# main.net
KiCad netlist of a schematic drawn in EAGLE
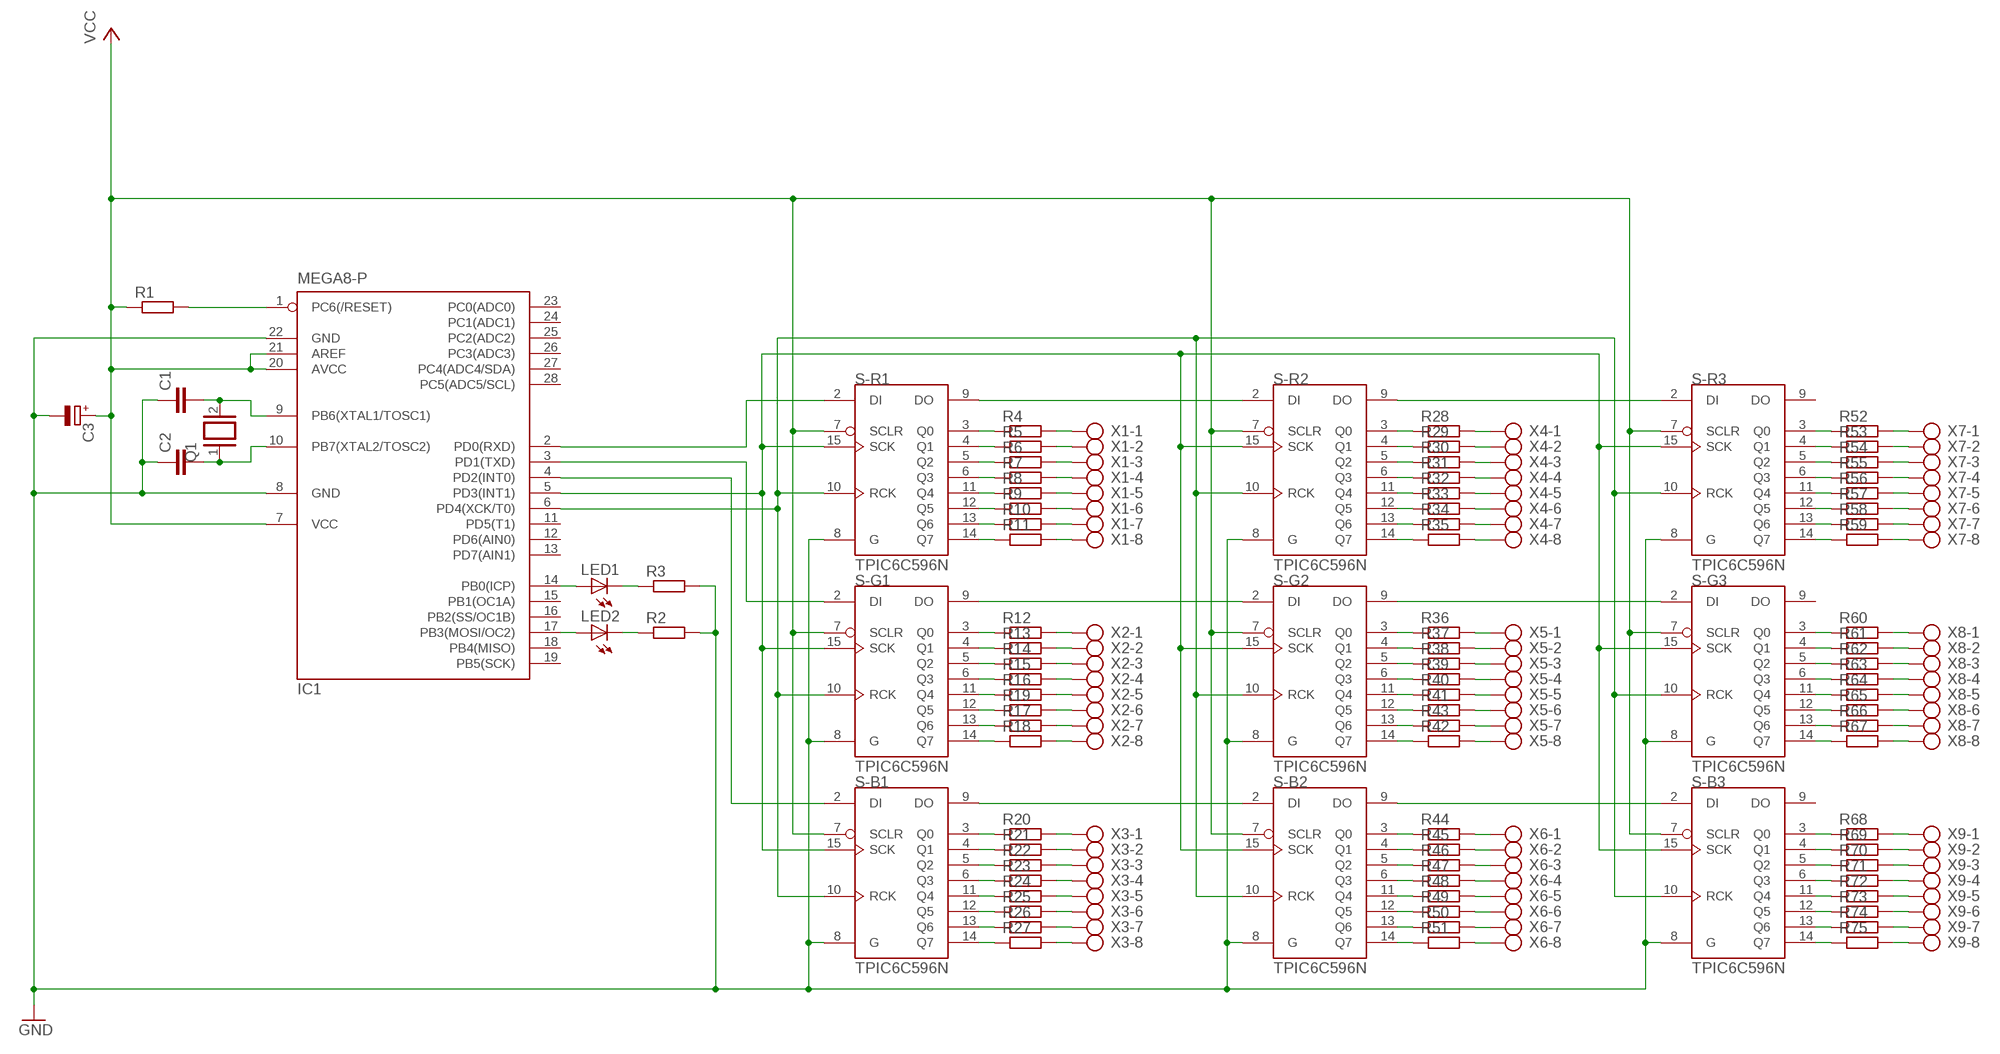
[diagram p0: schematic, sheet 1]

(export (version "E")
  (design (tool "Eeschema 10.0.6"))
  (components
    (comp (ref "C1")
      (value "C-EU025-025X050")
      (footprint "eagle-import:C025-025X050")
      (libsource (lib "eagle-import") (part "C-EU025-025X050"))
    )
    (comp (ref "C2")
      (value "C-EU025-025X050")
      (footprint "eagle-import:C025-025X050")
      (libsource (lib "eagle-import") (part "C-EU025-025X050"))
    )
    (comp (ref "C3")
      (value "CPOL-EUE2.5-7")
      (footprint "eagle-import:E2,5-7")
      (libsource (lib "eagle-import") (part "CPOL-EUE2.5-7"))
    )
    (comp (ref "IC1")
      (value "MEGA8-P")
      (footprint "eagle-import:DIL28-3")
      (libsource (lib "eagle-import") (part "MEGA8-P"))
    )
    (comp (ref "LED1")
      (value "LED3MM")
      (footprint "eagle-import:LED3MM")
      (libsource (lib "eagle-import") (part "LED3MM"))
    )
    (comp (ref "LED2")
      (value "LED3MM")
      (footprint "eagle-import:LED3MM")
      (libsource (lib "eagle-import") (part "LED3MM"))
    )
    (comp (ref "Q1")
      (value "XTAL/S")
      (footprint "eagle-import:QS")
      (libsource (lib "eagle-import") (part "XTAL/S"))
    )
    (comp (ref "R1")
      (value "R-EU_0207/2V")
      (footprint "eagle-import:0207_2V")
      (libsource (lib "eagle-import") (part "R-EU_0207/2V"))
    )
    (comp (ref "R2")
      (value "R-EU_0207/2V")
      (footprint "eagle-import:0207_2V")
      (libsource (lib "eagle-import") (part "R-EU_0207/2V"))
    )
    (comp (ref "R3")
      (value "R-EU_0207/2V")
      (footprint "eagle-import:0207_2V")
      (libsource (lib "eagle-import") (part "R-EU_0207/2V"))
    )
    (comp (ref "R4")
      (value "R-EU_0207/2V")
      (footprint "eagle-import:0207_2V")
      (libsource (lib "eagle-import") (part "R-EU_0207/2V"))
    )
    (comp (ref "R5")
      (value "R-EU_0207/2V")
      (footprint "eagle-import:0207_2V")
      (libsource (lib "eagle-import") (part "R-EU_0207/2V"))
    )
    (comp (ref "R6")
      (value "R-EU_0207/2V")
      (footprint "eagle-import:0207_2V")
      (libsource (lib "eagle-import") (part "R-EU_0207/2V"))
    )
    (comp (ref "R7")
      (value "R-EU_0207/2V")
      (footprint "eagle-import:0207_2V")
      (libsource (lib "eagle-import") (part "R-EU_0207/2V"))
    )
    (comp (ref "R8")
      (value "R-EU_0207/2V")
      (footprint "eagle-import:0207_2V")
      (libsource (lib "eagle-import") (part "R-EU_0207/2V"))
    )
    (comp (ref "R9")
      (value "R-EU_0207/2V")
      (footprint "eagle-import:0207_2V")
      (libsource (lib "eagle-import") (part "R-EU_0207/2V"))
    )
    (comp (ref "R10")
      (value "R-EU_0207/2V")
      (footprint "eagle-import:0207_2V")
      (libsource (lib "eagle-import") (part "R-EU_0207/2V"))
    )
    (comp (ref "R11")
      (value "R-EU_0207/2V")
      (footprint "eagle-import:0207_2V")
      (libsource (lib "eagle-import") (part "R-EU_0207/2V"))
    )
    (comp (ref "R12")
      (value "R-EU_0207/2V")
      (footprint "eagle-import:0207_2V")
      (libsource (lib "eagle-import") (part "R-EU_0207/2V"))
    )
    (comp (ref "R13")
      (value "R-EU_0207/2V")
      (footprint "eagle-import:0207_2V")
      (libsource (lib "eagle-import") (part "R-EU_0207/2V"))
    )
    (comp (ref "R14")
      (value "R-EU_0207/2V")
      (footprint "eagle-import:0207_2V")
      (libsource (lib "eagle-import") (part "R-EU_0207/2V"))
    )
    (comp (ref "R15")
      (value "R-EU_0207/2V")
      (footprint "eagle-import:0207_2V")
      (libsource (lib "eagle-import") (part "R-EU_0207/2V"))
    )
    (comp (ref "R16")
      (value "R-EU_0207/2V")
      (footprint "eagle-import:0207_2V")
      (libsource (lib "eagle-import") (part "R-EU_0207/2V"))
    )
    (comp (ref "R17")
      (value "R-EU_0207/2V")
      (footprint "eagle-import:0207_2V")
      (libsource (lib "eagle-import") (part "R-EU_0207/2V"))
    )
    (comp (ref "R18")
      (value "R-EU_0207/2V")
      (footprint "eagle-import:0207_2V")
      (libsource (lib "eagle-import") (part "R-EU_0207/2V"))
    )
    (comp (ref "R19")
      (value "R-EU_0207/2V")
      (footprint "eagle-import:0207_2V")
      (libsource (lib "eagle-import") (part "R-EU_0207/2V"))
    )
    (comp (ref "R20")
      (value "R-EU_0207/2V")
      (footprint "eagle-import:0207_2V")
      (libsource (lib "eagle-import") (part "R-EU_0207/2V"))
    )
    (comp (ref "R21")
      (value "R-EU_0207/2V")
      (footprint "eagle-import:0207_2V")
      (libsource (lib "eagle-import") (part "R-EU_0207/2V"))
    )
    (comp (ref "R22")
      (value "R-EU_0207/2V")
      (footprint "eagle-import:0207_2V")
      (libsource (lib "eagle-import") (part "R-EU_0207/2V"))
    )
    (comp (ref "R23")
      (value "R-EU_0207/2V")
      (footprint "eagle-import:0207_2V")
      (libsource (lib "eagle-import") (part "R-EU_0207/2V"))
    )
    (comp (ref "R24")
      (value "R-EU_0207/2V")
      (footprint "eagle-import:0207_2V")
      (libsource (lib "eagle-import") (part "R-EU_0207/2V"))
    )
    (comp (ref "R25")
      (value "R-EU_0207/2V")
      (footprint "eagle-import:0207_2V")
      (libsource (lib "eagle-import") (part "R-EU_0207/2V"))
    )
    (comp (ref "R26")
      (value "R-EU_0207/2V")
      (footprint "eagle-import:0207_2V")
      (libsource (lib "eagle-import") (part "R-EU_0207/2V"))
    )
    (comp (ref "R27")
      (value "R-EU_0207/2V")
      (footprint "eagle-import:0207_2V")
      (libsource (lib "eagle-import") (part "R-EU_0207/2V"))
    )
    (comp (ref "R28")
      (value "R-EU_0207/2V")
      (footprint "eagle-import:0207_2V")
      (libsource (lib "eagle-import") (part "R-EU_0207/2V"))
    )
    (comp (ref "R29")
      (value "R-EU_0207/2V")
      (footprint "eagle-import:0207_2V")
      (libsource (lib "eagle-import") (part "R-EU_0207/2V"))
    )
    (comp (ref "R30")
      (value "R-EU_0207/2V")
      (footprint "eagle-import:0207_2V")
      (libsource (lib "eagle-import") (part "R-EU_0207/2V"))
    )
    (comp (ref "R31")
      (value "R-EU_0207/2V")
      (footprint "eagle-import:0207_2V")
      (libsource (lib "eagle-import") (part "R-EU_0207/2V"))
    )
    (comp (ref "R32")
      (value "R-EU_0207/2V")
      (footprint "eagle-import:0207_2V")
      (libsource (lib "eagle-import") (part "R-EU_0207/2V"))
    )
    (comp (ref "R33")
      (value "R-EU_0207/2V")
      (footprint "eagle-import:0207_2V")
      (libsource (lib "eagle-import") (part "R-EU_0207/2V"))
    )
    (comp (ref "R34")
      (value "R-EU_0207/2V")
      (footprint "eagle-import:0207_2V")
      (libsource (lib "eagle-import") (part "R-EU_0207/2V"))
    )
    (comp (ref "R35")
      (value "R-EU_0207/2V")
      (footprint "eagle-import:0207_2V")
      (libsource (lib "eagle-import") (part "R-EU_0207/2V"))
    )
    (comp (ref "R36")
      (value "R-EU_0207/2V")
      (footprint "eagle-import:0207_2V")
      (libsource (lib "eagle-import") (part "R-EU_0207/2V"))
    )
    (comp (ref "R37")
      (value "R-EU_0207/2V")
      (footprint "eagle-import:0207_2V")
      (libsource (lib "eagle-import") (part "R-EU_0207/2V"))
    )
    (comp (ref "R38")
      (value "R-EU_0207/2V")
      (footprint "eagle-import:0207_2V")
      (libsource (lib "eagle-import") (part "R-EU_0207/2V"))
    )
    (comp (ref "R39")
      (value "R-EU_0207/2V")
      (footprint "eagle-import:0207_2V")
      (libsource (lib "eagle-import") (part "R-EU_0207/2V"))
    )
    (comp (ref "R40")
      (value "R-EU_0207/2V")
      (footprint "eagle-import:0207_2V")
      (libsource (lib "eagle-import") (part "R-EU_0207/2V"))
    )
    (comp (ref "R41")
      (value "R-EU_0207/2V")
      (footprint "eagle-import:0207_2V")
      (libsource (lib "eagle-import") (part "R-EU_0207/2V"))
    )
    (comp (ref "R42")
      (value "R-EU_0207/2V")
      (footprint "eagle-import:0207_2V")
      (libsource (lib "eagle-import") (part "R-EU_0207/2V"))
    )
    (comp (ref "R43")
      (value "R-EU_0207/2V")
      (footprint "eagle-import:0207_2V")
      (libsource (lib "eagle-import") (part "R-EU_0207/2V"))
    )
    (comp (ref "R44")
      (value "R-EU_0207/2V")
      (footprint "eagle-import:0207_2V")
      (libsource (lib "eagle-import") (part "R-EU_0207/2V"))
    )
    (comp (ref "R45")
      (value "R-EU_0207/2V")
      (footprint "eagle-import:0207_2V")
      (libsource (lib "eagle-import") (part "R-EU_0207/2V"))
    )
    (comp (ref "R46")
      (value "R-EU_0207/2V")
      (footprint "eagle-import:0207_2V")
      (libsource (lib "eagle-import") (part "R-EU_0207/2V"))
    )
    (comp (ref "R47")
      (value "R-EU_0207/2V")
      (footprint "eagle-import:0207_2V")
      (libsource (lib "eagle-import") (part "R-EU_0207/2V"))
    )
    (comp (ref "R48")
      (value "R-EU_0207/2V")
      (footprint "eagle-import:0207_2V")
      (libsource (lib "eagle-import") (part "R-EU_0207/2V"))
    )
    (comp (ref "R49")
      (value "R-EU_0207/2V")
      (footprint "eagle-import:0207_2V")
      (libsource (lib "eagle-import") (part "R-EU_0207/2V"))
    )
    (comp (ref "R50")
      (value "R-EU_0207/2V")
      (footprint "eagle-import:0207_2V")
      (libsource (lib "eagle-import") (part "R-EU_0207/2V"))
    )
    (comp (ref "R51")
      (value "R-EU_0207/2V")
      (footprint "eagle-import:0207_2V")
      (libsource (lib "eagle-import") (part "R-EU_0207/2V"))
    )
    (comp (ref "R52")
      (value "R-EU_0207/2V")
      (footprint "eagle-import:0207_2V")
      (libsource (lib "eagle-import") (part "R-EU_0207/2V"))
    )
    (comp (ref "R53")
      (value "R-EU_0207/2V")
      (footprint "eagle-import:0207_2V")
      (libsource (lib "eagle-import") (part "R-EU_0207/2V"))
    )
    (comp (ref "R54")
      (value "R-EU_0207/2V")
      (footprint "eagle-import:0207_2V")
      (libsource (lib "eagle-import") (part "R-EU_0207/2V"))
    )
    (comp (ref "R55")
      (value "R-EU_0207/2V")
      (footprint "eagle-import:0207_2V")
      (libsource (lib "eagle-import") (part "R-EU_0207/2V"))
    )
    (comp (ref "R56")
      (value "R-EU_0207/2V")
      (footprint "eagle-import:0207_2V")
      (libsource (lib "eagle-import") (part "R-EU_0207/2V"))
    )
    (comp (ref "R57")
      (value "R-EU_0207/2V")
      (footprint "eagle-import:0207_2V")
      (libsource (lib "eagle-import") (part "R-EU_0207/2V"))
    )
    (comp (ref "R58")
      (value "R-EU_0207/2V")
      (footprint "eagle-import:0207_2V")
      (libsource (lib "eagle-import") (part "R-EU_0207/2V"))
    )
    (comp (ref "R59")
      (value "R-EU_0207/2V")
      (footprint "eagle-import:0207_2V")
      (libsource (lib "eagle-import") (part "R-EU_0207/2V"))
    )
    (comp (ref "R60")
      (value "R-EU_0207/2V")
      (footprint "eagle-import:0207_2V")
      (libsource (lib "eagle-import") (part "R-EU_0207/2V"))
    )
    (comp (ref "R61")
      (value "R-EU_0207/2V")
      (footprint "eagle-import:0207_2V")
      (libsource (lib "eagle-import") (part "R-EU_0207/2V"))
    )
    (comp (ref "R62")
      (value "R-EU_0207/2V")
      (footprint "eagle-import:0207_2V")
      (libsource (lib "eagle-import") (part "R-EU_0207/2V"))
    )
    (comp (ref "R63")
      (value "R-EU_0207/2V")
      (footprint "eagle-import:0207_2V")
      (libsource (lib "eagle-import") (part "R-EU_0207/2V"))
    )
    (comp (ref "R64")
      (value "R-EU_0207/2V")
      (footprint "eagle-import:0207_2V")
      (libsource (lib "eagle-import") (part "R-EU_0207/2V"))
    )
    (comp (ref "R65")
      (value "R-EU_0207/2V")
      (footprint "eagle-import:0207_2V")
      (libsource (lib "eagle-import") (part "R-EU_0207/2V"))
    )
    (comp (ref "R66")
      (value "R-EU_0207/2V")
      (footprint "eagle-import:0207_2V")
      (libsource (lib "eagle-import") (part "R-EU_0207/2V"))
    )
    (comp (ref "R67")
      (value "R-EU_0207/2V")
      (footprint "eagle-import:0207_2V")
      (libsource (lib "eagle-import") (part "R-EU_0207/2V"))
    )
    (comp (ref "R68")
      (value "R-EU_0207/2V")
      (footprint "eagle-import:0207_2V")
      (libsource (lib "eagle-import") (part "R-EU_0207/2V"))
    )
    (comp (ref "R69")
      (value "R-EU_0207/2V")
      (footprint "eagle-import:0207_2V")
      (libsource (lib "eagle-import") (part "R-EU_0207/2V"))
    )
    (comp (ref "R70")
      (value "R-EU_0207/2V")
      (footprint "eagle-import:0207_2V")
      (libsource (lib "eagle-import") (part "R-EU_0207/2V"))
    )
    (comp (ref "R71")
      (value "R-EU_0207/2V")
      (footprint "eagle-import:0207_2V")
      (libsource (lib "eagle-import") (part "R-EU_0207/2V"))
    )
    (comp (ref "R72")
      (value "R-EU_0207/2V")
      (footprint "eagle-import:0207_2V")
      (libsource (lib "eagle-import") (part "R-EU_0207/2V"))
    )
    (comp (ref "R73")
      (value "R-EU_0207/2V")
      (footprint "eagle-import:0207_2V")
      (libsource (lib "eagle-import") (part "R-EU_0207/2V"))
    )
    (comp (ref "R74")
      (value "R-EU_0207/2V")
      (footprint "eagle-import:0207_2V")
      (libsource (lib "eagle-import") (part "R-EU_0207/2V"))
    )
    (comp (ref "R75")
      (value "R-EU_0207/2V")
      (footprint "eagle-import:0207_2V")
      (libsource (lib "eagle-import") (part "R-EU_0207/2V"))
    )
    (comp (ref "S-B1")
      (value "TPIC6C596N")
      (footprint "eagle-import:DIL16")
      (libsource (lib "eagle-import") (part "TPIC6C596N"))
    )
    (comp (ref "S-B2")
      (value "TPIC6C596N")
      (footprint "eagle-import:DIL16")
      (libsource (lib "eagle-import") (part "TPIC6C596N"))
    )
    (comp (ref "S-B3")
      (value "TPIC6C596N")
      (footprint "eagle-import:DIL16")
      (libsource (lib "eagle-import") (part "TPIC6C596N"))
    )
    (comp (ref "S-G1")
      (value "TPIC6C596N")
      (footprint "eagle-import:DIL16")
      (libsource (lib "eagle-import") (part "TPIC6C596N"))
    )
    (comp (ref "S-G2")
      (value "TPIC6C596N")
      (footprint "eagle-import:DIL16")
      (libsource (lib "eagle-import") (part "TPIC6C596N"))
    )
    (comp (ref "S-G3")
      (value "TPIC6C596N")
      (footprint "eagle-import:DIL16")
      (libsource (lib "eagle-import") (part "TPIC6C596N"))
    )
    (comp (ref "S-R1")
      (value "TPIC6C596N")
      (footprint "eagle-import:DIL16")
      (libsource (lib "eagle-import") (part "TPIC6C596N"))
    )
    (comp (ref "S-R2")
      (value "TPIC6C596N")
      (footprint "eagle-import:DIL16")
      (libsource (lib "eagle-import") (part "TPIC6C596N"))
    )
    (comp (ref "S-R3")
      (value "TPIC6C596N")
      (footprint "eagle-import:DIL16")
      (libsource (lib "eagle-import") (part "TPIC6C596N"))
    )
    (comp (ref "X1")
      (value "AK500/8-H")
      (footprint "eagle-import:AK500_8-H")
      (libsource (lib "eagle-import") (part "AK500/8-H"))
    )
    (comp (ref "X2")
      (value "AK500/8-H")
      (footprint "eagle-import:AK500_8-H")
      (libsource (lib "eagle-import") (part "AK500/8-H"))
    )
    (comp (ref "X3")
      (value "AK500/8-H")
      (footprint "eagle-import:AK500_8-H")
      (libsource (lib "eagle-import") (part "AK500/8-H"))
    )
    (comp (ref "X4")
      (value "AK500/8-H")
      (footprint "eagle-import:AK500_8-H")
      (libsource (lib "eagle-import") (part "AK500/8-H"))
    )
    (comp (ref "X5")
      (value "AK500/8-H")
      (footprint "eagle-import:AK500_8-H")
      (libsource (lib "eagle-import") (part "AK500/8-H"))
    )
    (comp (ref "X6")
      (value "AK500/8-H")
      (footprint "eagle-import:AK500_8-H")
      (libsource (lib "eagle-import") (part "AK500/8-H"))
    )
    (comp (ref "X7")
      (value "AK500/8-H")
      (footprint "eagle-import:AK500_8-H")
      (libsource (lib "eagle-import") (part "AK500/8-H"))
    )
    (comp (ref "X8")
      (value "AK500/8-H")
      (footprint "eagle-import:AK500_8-H")
      (libsource (lib "eagle-import") (part "AK500/8-H"))
    )
    (comp (ref "X9")
      (value "AK500/8-H")
      (footprint "eagle-import:AK500_8-H")
      (libsource (lib "eagle-import") (part "AK500/8-H"))
    )
  )
  (nets
    (net (code "1") (name "GND") (class "Default")
      (node (ref "C1") (pin "1") (pinfunction "1_1") (pintype "passive"))
      (node (ref "C2") (pin "1") (pinfunction "1_1") (pintype "passive"))
      (node (ref "C3") (pin "-") (pinfunction "-_-") (pintype "passive"))
      (node (ref "IC1") (pin "22") (pinfunction "GND_22") (pintype "power_in"))
      (node (ref "IC1") (pin "8") (pinfunction "GND_8") (pintype "power_in"))
      (node (ref "R2") (pin "2") (pinfunction "2_2") (pintype "passive"))
      (node (ref "R3") (pin "2") (pinfunction "2_2") (pintype "passive"))
      (node (ref "S-B1") (pin "8") (pinfunction "G_8") (pintype "input"))
      (node (ref "S-B2") (pin "8") (pinfunction "G_8") (pintype "input"))
      (node (ref "S-B3") (pin "8") (pinfunction "G_8") (pintype "input"))
      (node (ref "S-G1") (pin "8") (pinfunction "G_8") (pintype "input"))
      (node (ref "S-G2") (pin "8") (pinfunction "G_8") (pintype "input"))
      (node (ref "S-G3") (pin "8") (pinfunction "G_8") (pintype "input"))
      (node (ref "S-R1") (pin "8") (pinfunction "G_8") (pintype "input"))
      (node (ref "S-R2") (pin "8") (pinfunction "G_8") (pintype "input"))
      (node (ref "S-R3") (pin "8") (pinfunction "G_8") (pintype "input"))
    )
    (net (code "2") (name "Net-(IC1-PB0(ICP))") (class "Default")
      (node (ref "IC1") (pin "14") (pinfunction "PB0(ICP)_14") (pintype "bidirectional"))
      (node (ref "LED1") (pin "A") (pinfunction "A_A") (pintype "passive"))
    )
    (net (code "3") (name "Net-(IC1-PB3(MOSI{slash}OC2))") (class "Default")
      (node (ref "IC1") (pin "17") (pinfunction "PB3(MOSI/OC2)_17") (pintype "bidirectional"))
      (node (ref "LED2") (pin "A") (pinfunction "A_A") (pintype "passive"))
    )
    (net (code "4") (name "Net-(IC1-PB6(XTAL1{slash}TOSC1))") (class "Default")
      (node (ref "C1") (pin "2") (pinfunction "2_2") (pintype "passive"))
      (node (ref "IC1") (pin "9") (pinfunction "PB6(XTAL1/TOSC1)_9") (pintype "bidirectional"))
      (node (ref "Q1") (pin "2") (pinfunction "2_2") (pintype "passive"))
    )
    (net (code "5") (name "Net-(IC1-PB7(XTAL2{slash}TOSC2))") (class "Default")
      (node (ref "C2") (pin "2") (pinfunction "2_2") (pintype "passive"))
      (node (ref "IC1") (pin "10") (pinfunction "PB7(XTAL2/TOSC2)_10") (pintype "bidirectional"))
      (node (ref "Q1") (pin "1") (pinfunction "1_1") (pintype "passive"))
    )
    (net (code "6") (name "Net-(IC1-PC6({slash}RESET))") (class "Default")
      (node (ref "IC1") (pin "1") (pinfunction "PC6(/RESET)_1") (pintype "bidirectional"))
      (node (ref "R1") (pin "2") (pinfunction "2_2") (pintype "passive"))
    )
    (net (code "7") (name "Net-(IC1-PD0(RXD))") (class "Default")
      (node (ref "IC1") (pin "2") (pinfunction "PD0(RXD)_2") (pintype "bidirectional"))
      (node (ref "S-R1") (pin "2") (pinfunction "DI_2") (pintype "input"))
    )
    (net (code "8") (name "Net-(IC1-PD1(TXD))") (class "Default")
      (node (ref "IC1") (pin "3") (pinfunction "PD1(TXD)_3") (pintype "bidirectional"))
      (node (ref "S-G1") (pin "2") (pinfunction "DI_2") (pintype "input"))
    )
    (net (code "9") (name "Net-(IC1-PD2(INT0))") (class "Default")
      (node (ref "IC1") (pin "4") (pinfunction "PD2(INT0)_4") (pintype "bidirectional"))
      (node (ref "S-B1") (pin "2") (pinfunction "DI_2") (pintype "input"))
    )
    (net (code "10") (name "Net-(IC1-PD3(INT1))") (class "Default")
      (node (ref "IC1") (pin "5") (pinfunction "PD3(INT1)_5") (pintype "bidirectional"))
      (node (ref "S-B1") (pin "15") (pinfunction "SCK_15") (pintype "input"))
      (node (ref "S-B2") (pin "15") (pinfunction "SCK_15") (pintype "input"))
      (node (ref "S-B3") (pin "15") (pinfunction "SCK_15") (pintype "input"))
      (node (ref "S-G1") (pin "15") (pinfunction "SCK_15") (pintype "input"))
      (node (ref "S-G2") (pin "15") (pinfunction "SCK_15") (pintype "input"))
      (node (ref "S-G3") (pin "15") (pinfunction "SCK_15") (pintype "input"))
      (node (ref "S-R1") (pin "15") (pinfunction "SCK_15") (pintype "input"))
      (node (ref "S-R2") (pin "15") (pinfunction "SCK_15") (pintype "input"))
      (node (ref "S-R3") (pin "15") (pinfunction "SCK_15") (pintype "input"))
    )
    (net (code "11") (name "Net-(IC1-PD4(XCK{slash}T0))") (class "Default")
      (node (ref "IC1") (pin "6") (pinfunction "PD4(XCK/T0)_6") (pintype "bidirectional"))
      (node (ref "S-B1") (pin "10") (pinfunction "RCK_10") (pintype "input"))
      (node (ref "S-B2") (pin "10") (pinfunction "RCK_10") (pintype "input"))
      (node (ref "S-B3") (pin "10") (pinfunction "RCK_10") (pintype "input"))
      (node (ref "S-G1") (pin "10") (pinfunction "RCK_10") (pintype "input"))
      (node (ref "S-G2") (pin "10") (pinfunction "RCK_10") (pintype "input"))
      (node (ref "S-G3") (pin "10") (pinfunction "RCK_10") (pintype "input"))
      (node (ref "S-R1") (pin "10") (pinfunction "RCK_10") (pintype "input"))
      (node (ref "S-R2") (pin "10") (pinfunction "RCK_10") (pintype "input"))
      (node (ref "S-R3") (pin "10") (pinfunction "RCK_10") (pintype "input"))
    )
    (net (code "12") (name "Net-(LED1-C)") (class "Default")
      (node (ref "LED1") (pin "K") (pinfunction "C_K") (pintype "passive"))
      (node (ref "R3") (pin "1") (pinfunction "1_1") (pintype "passive"))
    )
    (net (code "13") (name "Net-(LED2-C)") (class "Default")
      (node (ref "LED2") (pin "K") (pinfunction "C_K") (pintype "passive"))
      (node (ref "R2") (pin "1") (pinfunction "1_1") (pintype "passive"))
    )
    (net (code "14") (name "Net-(S-B1A-DO)") (class "Default")
      (node (ref "S-B1") (pin "9") (pinfunction "DO_9") (pintype "output"))
      (node (ref "S-B2") (pin "2") (pinfunction "DI_2") (pintype "input"))
    )
    (net (code "15") (name "Net-(S-B1A-Q0)") (class "Default")
      (node (ref "R20") (pin "1") (pinfunction "1_1") (pintype "passive"))
      (node (ref "S-B1") (pin "3") (pinfunction "Q0_3") (pintype "open_collector"))
    )
    (net (code "16") (name "Net-(S-B1A-Q1)") (class "Default")
      (node (ref "R21") (pin "1") (pinfunction "1_1") (pintype "passive"))
      (node (ref "S-B1") (pin "4") (pinfunction "Q1_4") (pintype "open_collector"))
    )
    (net (code "17") (name "Net-(S-B1A-Q2)") (class "Default")
      (node (ref "R22") (pin "1") (pinfunction "1_1") (pintype "passive"))
      (node (ref "S-B1") (pin "5") (pinfunction "Q2_5") (pintype "open_collector"))
    )
    (net (code "18") (name "Net-(S-B1A-Q3)") (class "Default")
      (node (ref "R23") (pin "1") (pinfunction "1_1") (pintype "passive"))
      (node (ref "S-B1") (pin "6") (pinfunction "Q3_6") (pintype "open_collector"))
    )
    (net (code "19") (name "Net-(S-B1A-Q4)") (class "Default")
      (node (ref "R24") (pin "1") (pinfunction "1_1") (pintype "passive"))
      (node (ref "S-B1") (pin "11") (pinfunction "Q4_11") (pintype "open_collector"))
    )
    (net (code "20") (name "Net-(S-B1A-Q5)") (class "Default")
      (node (ref "R25") (pin "1") (pinfunction "1_1") (pintype "passive"))
      (node (ref "S-B1") (pin "12") (pinfunction "Q5_12") (pintype "open_collector"))
    )
    (net (code "21") (name "Net-(S-B1A-Q6)") (class "Default")
      (node (ref "R26") (pin "1") (pinfunction "1_1") (pintype "passive"))
      (node (ref "S-B1") (pin "13") (pinfunction "Q6_13") (pintype "open_collector"))
    )
    (net (code "22") (name "Net-(S-B1A-Q7)") (class "Default")
      (node (ref "R27") (pin "1") (pinfunction "1_1") (pintype "passive"))
      (node (ref "S-B1") (pin "14") (pinfunction "Q7_14") (pintype "open_collector"))
    )
    (net (code "23") (name "Net-(S-B2A-DO)") (class "Default")
      (node (ref "S-B2") (pin "9") (pinfunction "DO_9") (pintype "output"))
      (node (ref "S-B3") (pin "2") (pinfunction "DI_2") (pintype "input"))
    )
    (net (code "24") (name "Net-(S-B2A-Q0)") (class "Default")
      (node (ref "R44") (pin "1") (pinfunction "1_1") (pintype "passive"))
      (node (ref "S-B2") (pin "3") (pinfunction "Q0_3") (pintype "open_collector"))
    )
    (net (code "25") (name "Net-(S-B2A-Q1)") (class "Default")
      (node (ref "R45") (pin "1") (pinfunction "1_1") (pintype "passive"))
      (node (ref "S-B2") (pin "4") (pinfunction "Q1_4") (pintype "open_collector"))
    )
    (net (code "26") (name "Net-(S-B2A-Q2)") (class "Default")
      (node (ref "R46") (pin "1") (pinfunction "1_1") (pintype "passive"))
      (node (ref "S-B2") (pin "5") (pinfunction "Q2_5") (pintype "open_collector"))
    )
    (net (code "27") (name "Net-(S-B2A-Q3)") (class "Default")
      (node (ref "R47") (pin "1") (pinfunction "1_1") (pintype "passive"))
      (node (ref "S-B2") (pin "6") (pinfunction "Q3_6") (pintype "open_collector"))
    )
    (net (code "28") (name "Net-(S-B2A-Q4)") (class "Default")
      (node (ref "R48") (pin "1") (pinfunction "1_1") (pintype "passive"))
      (node (ref "S-B2") (pin "11") (pinfunction "Q4_11") (pintype "open_collector"))
    )
    (net (code "29") (name "Net-(S-B2A-Q5)") (class "Default")
      (node (ref "R49") (pin "1") (pinfunction "1_1") (pintype "passive"))
      (node (ref "S-B2") (pin "12") (pinfunction "Q5_12") (pintype "open_collector"))
    )
    (net (code "30") (name "Net-(S-B2A-Q6)") (class "Default")
      (node (ref "R50") (pin "1") (pinfunction "1_1") (pintype "passive"))
      (node (ref "S-B2") (pin "13") (pinfunction "Q6_13") (pintype "open_collector"))
    )
    (net (code "31") (name "Net-(S-B2A-Q7)") (class "Default")
      (node (ref "R51") (pin "1") (pinfunction "1_1") (pintype "passive"))
      (node (ref "S-B2") (pin "14") (pinfunction "Q7_14") (pintype "open_collector"))
    )
    (net (code "32") (name "Net-(S-B3A-Q0)") (class "Default")
      (node (ref "R68") (pin "1") (pinfunction "1_1") (pintype "passive"))
      (node (ref "S-B3") (pin "3") (pinfunction "Q0_3") (pintype "open_collector"))
    )
    (net (code "33") (name "Net-(S-B3A-Q1)") (class "Default")
      (node (ref "R69") (pin "1") (pinfunction "1_1") (pintype "passive"))
      (node (ref "S-B3") (pin "4") (pinfunction "Q1_4") (pintype "open_collector"))
    )
    (net (code "34") (name "Net-(S-B3A-Q2)") (class "Default")
      (node (ref "R70") (pin "1") (pinfunction "1_1") (pintype "passive"))
      (node (ref "S-B3") (pin "5") (pinfunction "Q2_5") (pintype "open_collector"))
    )
    (net (code "35") (name "Net-(S-B3A-Q3)") (class "Default")
      (node (ref "R71") (pin "1") (pinfunction "1_1") (pintype "passive"))
      (node (ref "S-B3") (pin "6") (pinfunction "Q3_6") (pintype "open_collector"))
    )
    (net (code "36") (name "Net-(S-B3A-Q4)") (class "Default")
      (node (ref "R72") (pin "1") (pinfunction "1_1") (pintype "passive"))
      (node (ref "S-B3") (pin "11") (pinfunction "Q4_11") (pintype "open_collector"))
    )
    (net (code "37") (name "Net-(S-B3A-Q5)") (class "Default")
      (node (ref "R73") (pin "1") (pinfunction "1_1") (pintype "passive"))
      (node (ref "S-B3") (pin "12") (pinfunction "Q5_12") (pintype "open_collector"))
    )
    (net (code "38") (name "Net-(S-B3A-Q6)") (class "Default")
      (node (ref "R74") (pin "1") (pinfunction "1_1") (pintype "passive"))
      (node (ref "S-B3") (pin "13") (pinfunction "Q6_13") (pintype "open_collector"))
    )
    (net (code "39") (name "Net-(S-B3A-Q7)") (class "Default")
      (node (ref "R75") (pin "1") (pinfunction "1_1") (pintype "passive"))
      (node (ref "S-B3") (pin "14") (pinfunction "Q7_14") (pintype "open_collector"))
    )
    (net (code "40") (name "Net-(S-G1A-DO)") (class "Default")
      (node (ref "S-G1") (pin "9") (pinfunction "DO_9") (pintype "output"))
      (node (ref "S-G2") (pin "2") (pinfunction "DI_2") (pintype "input"))
    )
    (net (code "41") (name "Net-(S-G1A-Q0)") (class "Default")
      (node (ref "R12") (pin "1") (pinfunction "1_1") (pintype "passive"))
      (node (ref "S-G1") (pin "3") (pinfunction "Q0_3") (pintype "open_collector"))
    )
    (net (code "42") (name "Net-(S-G1A-Q1)") (class "Default")
      (node (ref "R13") (pin "1") (pinfunction "1_1") (pintype "passive"))
      (node (ref "S-G1") (pin "4") (pinfunction "Q1_4") (pintype "open_collector"))
    )
    (net (code "43") (name "Net-(S-G1A-Q2)") (class "Default")
      (node (ref "R14") (pin "1") (pinfunction "1_1") (pintype "passive"))
      (node (ref "S-G1") (pin "5") (pinfunction "Q2_5") (pintype "open_collector"))
    )
    (net (code "44") (name "Net-(S-G1A-Q3)") (class "Default")
      (node (ref "R15") (pin "1") (pinfunction "1_1") (pintype "passive"))
      (node (ref "S-G1") (pin "6") (pinfunction "Q3_6") (pintype "open_collector"))
    )
    (net (code "45") (name "Net-(S-G1A-Q4)") (class "Default")
      (node (ref "R16") (pin "1") (pinfunction "1_1") (pintype "passive"))
      (node (ref "S-G1") (pin "11") (pinfunction "Q4_11") (pintype "open_collector"))
    )
    (net (code "46") (name "Net-(S-G1A-Q5)") (class "Default")
      (node (ref "R19") (pin "1") (pinfunction "1_1") (pintype "passive"))
      (node (ref "S-G1") (pin "12") (pinfunction "Q5_12") (pintype "open_collector"))
    )
    (net (code "47") (name "Net-(S-G1A-Q6)") (class "Default")
      (node (ref "R17") (pin "1") (pinfunction "1_1") (pintype "passive"))
      (node (ref "S-G1") (pin "13") (pinfunction "Q6_13") (pintype "open_collector"))
    )
    (net (code "48") (name "Net-(S-G1A-Q7)") (class "Default")
      (node (ref "R18") (pin "1") (pinfunction "1_1") (pintype "passive"))
      (node (ref "S-G1") (pin "14") (pinfunction "Q7_14") (pintype "open_collector"))
    )
    (net (code "49") (name "Net-(S-G2A-DO)") (class "Default")
      (node (ref "S-G2") (pin "9") (pinfunction "DO_9") (pintype "output"))
      (node (ref "S-G3") (pin "2") (pinfunction "DI_2") (pintype "input"))
    )
    (net (code "50") (name "Net-(S-G2A-Q0)") (class "Default")
      (node (ref "R36") (pin "1") (pinfunction "1_1") (pintype "passive"))
      (node (ref "S-G2") (pin "3") (pinfunction "Q0_3") (pintype "open_collector"))
    )
    (net (code "51") (name "Net-(S-G2A-Q1)") (class "Default")
      (node (ref "R37") (pin "1") (pinfunction "1_1") (pintype "passive"))
      (node (ref "S-G2") (pin "4") (pinfunction "Q1_4") (pintype "open_collector"))
    )
    (net (code "52") (name "Net-(S-G2A-Q2)") (class "Default")
      (node (ref "R38") (pin "1") (pinfunction "1_1") (pintype "passive"))
      (node (ref "S-G2") (pin "5") (pinfunction "Q2_5") (pintype "open_collector"))
    )
    (net (code "53") (name "Net-(S-G2A-Q3)") (class "Default")
      (node (ref "R39") (pin "1") (pinfunction "1_1") (pintype "passive"))
      (node (ref "S-G2") (pin "6") (pinfunction "Q3_6") (pintype "open_collector"))
    )
    (net (code "54") (name "Net-(S-G2A-Q4)") (class "Default")
      (node (ref "R40") (pin "1") (pinfunction "1_1") (pintype "passive"))
      (node (ref "S-G2") (pin "11") (pinfunction "Q4_11") (pintype "open_collector"))
    )
    (net (code "55") (name "Net-(S-G2A-Q5)") (class "Default")
      (node (ref "R41") (pin "1") (pinfunction "1_1") (pintype "passive"))
      (node (ref "S-G2") (pin "12") (pinfunction "Q5_12") (pintype "open_collector"))
    )
    (net (code "56") (name "Net-(S-G2A-Q6)") (class "Default")
      (node (ref "R43") (pin "1") (pinfunction "1_1") (pintype "passive"))
      (node (ref "S-G2") (pin "13") (pinfunction "Q6_13") (pintype "open_collector"))
    )
    (net (code "57") (name "Net-(S-G2A-Q7)") (class "Default")
      (node (ref "R42") (pin "1") (pinfunction "1_1") (pintype "passive"))
      (node (ref "S-G2") (pin "14") (pinfunction "Q7_14") (pintype "open_collector"))
    )
    (net (code "58") (name "Net-(S-G3A-Q0)") (class "Default")
      (node (ref "R60") (pin "1") (pinfunction "1_1") (pintype "passive"))
      (node (ref "S-G3") (pin "3") (pinfunction "Q0_3") (pintype "open_collector"))
    )
    (net (code "59") (name "Net-(S-G3A-Q1)") (class "Default")
      (node (ref "R61") (pin "1") (pinfunction "1_1") (pintype "passive"))
      (node (ref "S-G3") (pin "4") (pinfunction "Q1_4") (pintype "open_collector"))
    )
    (net (code "60") (name "Net-(S-G3A-Q2)") (class "Default")
      (node (ref "R62") (pin "1") (pinfunction "1_1") (pintype "passive"))
      (node (ref "S-G3") (pin "5") (pinfunction "Q2_5") (pintype "open_collector"))
    )
    (net (code "61") (name "Net-(S-G3A-Q3)") (class "Default")
      (node (ref "R63") (pin "1") (pinfunction "1_1") (pintype "passive"))
      (node (ref "S-G3") (pin "6") (pinfunction "Q3_6") (pintype "open_collector"))
    )
    (net (code "62") (name "Net-(S-G3A-Q4)") (class "Default")
      (node (ref "R64") (pin "1") (pinfunction "1_1") (pintype "passive"))
      (node (ref "S-G3") (pin "11") (pinfunction "Q4_11") (pintype "open_collector"))
    )
    (net (code "63") (name "Net-(S-G3A-Q5)") (class "Default")
      (node (ref "R65") (pin "1") (pinfunction "1_1") (pintype "passive"))
      (node (ref "S-G3") (pin "12") (pinfunction "Q5_12") (pintype "open_collector"))
    )
    (net (code "64") (name "Net-(S-G3A-Q6)") (class "Default")
      (node (ref "R66") (pin "1") (pinfunction "1_1") (pintype "passive"))
      (node (ref "S-G3") (pin "13") (pinfunction "Q6_13") (pintype "open_collector"))
    )
    (net (code "65") (name "Net-(S-G3A-Q7)") (class "Default")
      (node (ref "R67") (pin "1") (pinfunction "1_1") (pintype "passive"))
      (node (ref "S-G3") (pin "14") (pinfunction "Q7_14") (pintype "open_collector"))
    )
    (net (code "66") (name "Net-(S-R1A-DO)") (class "Default")
      (node (ref "S-R1") (pin "9") (pinfunction "DO_9") (pintype "output"))
      (node (ref "S-R2") (pin "2") (pinfunction "DI_2") (pintype "input"))
    )
    (net (code "67") (name "Net-(S-R1A-Q0)") (class "Default")
      (node (ref "R4") (pin "1") (pinfunction "1_1") (pintype "passive"))
      (node (ref "S-R1") (pin "3") (pinfunction "Q0_3") (pintype "open_collector"))
    )
    (net (code "68") (name "Net-(S-R1A-Q1)") (class "Default")
      (node (ref "R5") (pin "1") (pinfunction "1_1") (pintype "passive"))
      (node (ref "S-R1") (pin "4") (pinfunction "Q1_4") (pintype "open_collector"))
    )
    (net (code "69") (name "Net-(S-R1A-Q2)") (class "Default")
      (node (ref "R6") (pin "1") (pinfunction "1_1") (pintype "passive"))
      (node (ref "S-R1") (pin "5") (pinfunction "Q2_5") (pintype "open_collector"))
    )
    (net (code "70") (name "Net-(S-R1A-Q3)") (class "Default")
      (node (ref "R7") (pin "1") (pinfunction "1_1") (pintype "passive"))
      (node (ref "S-R1") (pin "6") (pinfunction "Q3_6") (pintype "open_collector"))
    )
    (net (code "71") (name "Net-(S-R1A-Q4)") (class "Default")
      (node (ref "R8") (pin "1") (pinfunction "1_1") (pintype "passive"))
      (node (ref "S-R1") (pin "11") (pinfunction "Q4_11") (pintype "open_collector"))
    )
    (net (code "72") (name "Net-(S-R1A-Q5)") (class "Default")
      (node (ref "R9") (pin "1") (pinfunction "1_1") (pintype "passive"))
      (node (ref "S-R1") (pin "12") (pinfunction "Q5_12") (pintype "open_collector"))
    )
    (net (code "73") (name "Net-(S-R1A-Q6)") (class "Default")
      (node (ref "R10") (pin "1") (pinfunction "1_1") (pintype "passive"))
      (node (ref "S-R1") (pin "13") (pinfunction "Q6_13") (pintype "open_collector"))
    )
    (net (code "74") (name "Net-(S-R1A-Q7)") (class "Default")
      (node (ref "R11") (pin "1") (pinfunction "1_1") (pintype "passive"))
      (node (ref "S-R1") (pin "14") (pinfunction "Q7_14") (pintype "open_collector"))
    )
    (net (code "75") (name "Net-(S-R2A-DO)") (class "Default")
      (node (ref "S-R2") (pin "9") (pinfunction "DO_9") (pintype "output"))
      (node (ref "S-R3") (pin "2") (pinfunction "DI_2") (pintype "input"))
    )
    (net (code "76") (name "Net-(S-R2A-Q0)") (class "Default")
      (node (ref "R28") (pin "1") (pinfunction "1_1") (pintype "passive"))
      (node (ref "S-R2") (pin "3") (pinfunction "Q0_3") (pintype "open_collector"))
    )
    (net (code "77") (name "Net-(S-R2A-Q1)") (class "Default")
      (node (ref "R29") (pin "1") (pinfunction "1_1") (pintype "passive"))
      (node (ref "S-R2") (pin "4") (pinfunction "Q1_4") (pintype "open_collector"))
    )
    (net (code "78") (name "Net-(S-R2A-Q2)") (class "Default")
      (node (ref "R30") (pin "1") (pinfunction "1_1") (pintype "passive"))
      (node (ref "S-R2") (pin "5") (pinfunction "Q2_5") (pintype "open_collector"))
    )
    (net (code "79") (name "Net-(S-R2A-Q3)") (class "Default")
      (node (ref "R31") (pin "1") (pinfunction "1_1") (pintype "passive"))
      (node (ref "S-R2") (pin "6") (pinfunction "Q3_6") (pintype "open_collector"))
    )
    (net (code "80") (name "Net-(S-R2A-Q4)") (class "Default")
      (node (ref "R32") (pin "1") (pinfunction "1_1") (pintype "passive"))
      (node (ref "S-R2") (pin "11") (pinfunction "Q4_11") (pintype "open_collector"))
    )
    (net (code "81") (name "Net-(S-R2A-Q5)") (class "Default")
      (node (ref "R33") (pin "1") (pinfunction "1_1") (pintype "passive"))
      (node (ref "S-R2") (pin "12") (pinfunction "Q5_12") (pintype "open_collector"))
    )
    (net (code "82") (name "Net-(S-R2A-Q6)") (class "Default")
      (node (ref "R34") (pin "1") (pinfunction "1_1") (pintype "passive"))
      (node (ref "S-R2") (pin "13") (pinfunction "Q6_13") (pintype "open_collector"))
    )
    (net (code "83") (name "Net-(S-R2A-Q7)") (class "Default")
      (node (ref "R35") (pin "1") (pinfunction "1_1") (pintype "passive"))
      (node (ref "S-R2") (pin "14") (pinfunction "Q7_14") (pintype "open_collector"))
    )
    (net (code "84") (name "Net-(S-R3A-Q0)") (class "Default")
      (node (ref "R52") (pin "1") (pinfunction "1_1") (pintype "passive"))
      (node (ref "S-R3") (pin "3") (pinfunction "Q0_3") (pintype "open_collector"))
    )
    (net (code "85") (name "Net-(S-R3A-Q1)") (class "Default")
      (node (ref "R53") (pin "1") (pinfunction "1_1") (pintype "passive"))
      (node (ref "S-R3") (pin "4") (pinfunction "Q1_4") (pintype "open_collector"))
    )
    (net (code "86") (name "Net-(S-R3A-Q2)") (class "Default")
      (node (ref "R54") (pin "1") (pinfunction "1_1") (pintype "passive"))
      (node (ref "S-R3") (pin "5") (pinfunction "Q2_5") (pintype "open_collector"))
    )
    (net (code "87") (name "Net-(S-R3A-Q3)") (class "Default")
      (node (ref "R55") (pin "1") (pinfunction "1_1") (pintype "passive"))
      (node (ref "S-R3") (pin "6") (pinfunction "Q3_6") (pintype "open_collector"))
    )
    (net (code "88") (name "Net-(S-R3A-Q4)") (class "Default")
      (node (ref "R56") (pin "1") (pinfunction "1_1") (pintype "passive"))
      (node (ref "S-R3") (pin "11") (pinfunction "Q4_11") (pintype "open_collector"))
    )
    (net (code "89") (name "Net-(S-R3A-Q5)") (class "Default")
      (node (ref "R57") (pin "1") (pinfunction "1_1") (pintype "passive"))
      (node (ref "S-R3") (pin "12") (pinfunction "Q5_12") (pintype "open_collector"))
    )
    (net (code "90") (name "Net-(S-R3A-Q6)") (class "Default")
      (node (ref "R58") (pin "1") (pinfunction "1_1") (pintype "passive"))
      (node (ref "S-R3") (pin "13") (pinfunction "Q6_13") (pintype "open_collector"))
    )
    (net (code "91") (name "Net-(S-R3A-Q7)") (class "Default")
      (node (ref "R59") (pin "1") (pinfunction "1_1") (pintype "passive"))
      (node (ref "S-R3") (pin "14") (pinfunction "Q7_14") (pintype "open_collector"))
    )
    (net (code "92") (name "Net-(X1A-KL)") (class "Default")
      (node (ref "R4") (pin "2") (pinfunction "2_2") (pintype "passive"))
      (node (ref "X1") (pin "1") (pinfunction "KL_1") (pintype "passive"))
    )
    (net (code "93") (name "Net-(X1B-KL)") (class "Default")
      (node (ref "R5") (pin "2") (pinfunction "2_2") (pintype "passive"))
      (node (ref "X1") (pin "2") (pinfunction "KL_2") (pintype "passive"))
    )
    (net (code "94") (name "Net-(X1C-KL)") (class "Default")
      (node (ref "R6") (pin "2") (pinfunction "2_2") (pintype "passive"))
      (node (ref "X1") (pin "3") (pinfunction "KL_3") (pintype "passive"))
    )
    (net (code "95") (name "Net-(X1D-KL)") (class "Default")
      (node (ref "R7") (pin "2") (pinfunction "2_2") (pintype "passive"))
      (node (ref "X1") (pin "4") (pinfunction "KL_4") (pintype "passive"))
    )
    (net (code "96") (name "Net-(X1E-KL)") (class "Default")
      (node (ref "R8") (pin "2") (pinfunction "2_2") (pintype "passive"))
      (node (ref "X1") (pin "5") (pinfunction "KL_5") (pintype "passive"))
    )
    (net (code "97") (name "Net-(X1F-KL)") (class "Default")
      (node (ref "R9") (pin "2") (pinfunction "2_2") (pintype "passive"))
      (node (ref "X1") (pin "6") (pinfunction "KL_6") (pintype "passive"))
    )
    (net (code "98") (name "Net-(X1G-KL)") (class "Default")
      (node (ref "R10") (pin "2") (pinfunction "2_2") (pintype "passive"))
      (node (ref "X1") (pin "7") (pinfunction "KL_7") (pintype "passive"))
    )
    (net (code "99") (name "Net-(X1H-KL)") (class "Default")
      (node (ref "R11") (pin "2") (pinfunction "2_2") (pintype "passive"))
      (node (ref "X1") (pin "8") (pinfunction "KL_8") (pintype "passive"))
    )
    (net (code "100") (name "Net-(X2A-KL)") (class "Default")
      (node (ref "R12") (pin "2") (pinfunction "2_2") (pintype "passive"))
      (node (ref "X2") (pin "1") (pinfunction "KL_1") (pintype "passive"))
    )
    (net (code "101") (name "Net-(X2B-KL)") (class "Default")
      (node (ref "R13") (pin "2") (pinfunction "2_2") (pintype "passive"))
      (node (ref "X2") (pin "2") (pinfunction "KL_2") (pintype "passive"))
    )
    (net (code "102") (name "Net-(X2C-KL)") (class "Default")
      (node (ref "R14") (pin "2") (pinfunction "2_2") (pintype "passive"))
      (node (ref "X2") (pin "3") (pinfunction "KL_3") (pintype "passive"))
    )
    (net (code "103") (name "Net-(X2D-KL)") (class "Default")
      (node (ref "R15") (pin "2") (pinfunction "2_2") (pintype "passive"))
      (node (ref "X2") (pin "4") (pinfunction "KL_4") (pintype "passive"))
    )
    (net (code "104") (name "Net-(X2E-KL)") (class "Default")
      (node (ref "R16") (pin "2") (pinfunction "2_2") (pintype "passive"))
      (node (ref "X2") (pin "5") (pinfunction "KL_5") (pintype "passive"))
    )
    (net (code "105") (name "Net-(X2F-KL)") (class "Default")
      (node (ref "R19") (pin "2") (pinfunction "2_2") (pintype "passive"))
      (node (ref "X2") (pin "6") (pinfunction "KL_6") (pintype "passive"))
    )
    (net (code "106") (name "Net-(X2G-KL)") (class "Default")
      (node (ref "R17") (pin "2") (pinfunction "2_2") (pintype "passive"))
      (node (ref "X2") (pin "7") (pinfunction "KL_7") (pintype "passive"))
    )
    (net (code "107") (name "Net-(X2H-KL)") (class "Default")
      (node (ref "R18") (pin "2") (pinfunction "2_2") (pintype "passive"))
      (node (ref "X2") (pin "8") (pinfunction "KL_8") (pintype "passive"))
    )
    (net (code "108") (name "Net-(X3A-KL)") (class "Default")
      (node (ref "R20") (pin "2") (pinfunction "2_2") (pintype "passive"))
      (node (ref "X3") (pin "1") (pinfunction "KL_1") (pintype "passive"))
    )
    (net (code "109") (name "Net-(X3B-KL)") (class "Default")
      (node (ref "R21") (pin "2") (pinfunction "2_2") (pintype "passive"))
      (node (ref "X3") (pin "2") (pinfunction "KL_2") (pintype "passive"))
    )
    (net (code "110") (name "Net-(X3C-KL)") (class "Default")
      (node (ref "R22") (pin "2") (pinfunction "2_2") (pintype "passive"))
      (node (ref "X3") (pin "3") (pinfunction "KL_3") (pintype "passive"))
    )
    (net (code "111") (name "Net-(X3D-KL)") (class "Default")
      (node (ref "R23") (pin "2") (pinfunction "2_2") (pintype "passive"))
      (node (ref "X3") (pin "4") (pinfunction "KL_4") (pintype "passive"))
    )
    (net (code "112") (name "Net-(X3E-KL)") (class "Default")
      (node (ref "R24") (pin "2") (pinfunction "2_2") (pintype "passive"))
      (node (ref "X3") (pin "5") (pinfunction "KL_5") (pintype "passive"))
    )
    (net (code "113") (name "Net-(X3F-KL)") (class "Default")
      (node (ref "R25") (pin "2") (pinfunction "2_2") (pintype "passive"))
      (node (ref "X3") (pin "6") (pinfunction "KL_6") (pintype "passive"))
    )
    (net (code "114") (name "Net-(X3G-KL)") (class "Default")
      (node (ref "R26") (pin "2") (pinfunction "2_2") (pintype "passive"))
      (node (ref "X3") (pin "7") (pinfunction "KL_7") (pintype "passive"))
    )
    (net (code "115") (name "Net-(X3H-KL)") (class "Default")
      (node (ref "R27") (pin "2") (pinfunction "2_2") (pintype "passive"))
      (node (ref "X3") (pin "8") (pinfunction "KL_8") (pintype "passive"))
    )
    (net (code "116") (name "Net-(X4A-KL)") (class "Default")
      (node (ref "R28") (pin "2") (pinfunction "2_2") (pintype "passive"))
      (node (ref "X4") (pin "1") (pinfunction "KL_1") (pintype "passive"))
    )
    (net (code "117") (name "Net-(X4B-KL)") (class "Default")
      (node (ref "R29") (pin "2") (pinfunction "2_2") (pintype "passive"))
      (node (ref "X4") (pin "2") (pinfunction "KL_2") (pintype "passive"))
    )
    (net (code "118") (name "Net-(X4C-KL)") (class "Default")
      (node (ref "R30") (pin "2") (pinfunction "2_2") (pintype "passive"))
      (node (ref "X4") (pin "3") (pinfunction "KL_3") (pintype "passive"))
    )
    (net (code "119") (name "Net-(X4D-KL)") (class "Default")
      (node (ref "R31") (pin "2") (pinfunction "2_2") (pintype "passive"))
      (node (ref "X4") (pin "4") (pinfunction "KL_4") (pintype "passive"))
    )
    (net (code "120") (name "Net-(X4E-KL)") (class "Default")
      (node (ref "R32") (pin "2") (pinfunction "2_2") (pintype "passive"))
      (node (ref "X4") (pin "5") (pinfunction "KL_5") (pintype "passive"))
    )
    (net (code "121") (name "Net-(X4F-KL)") (class "Default")
      (node (ref "R33") (pin "2") (pinfunction "2_2") (pintype "passive"))
      (node (ref "X4") (pin "6") (pinfunction "KL_6") (pintype "passive"))
    )
    (net (code "122") (name "Net-(X4G-KL)") (class "Default")
      (node (ref "R34") (pin "2") (pinfunction "2_2") (pintype "passive"))
      (node (ref "X4") (pin "7") (pinfunction "KL_7") (pintype "passive"))
    )
    (net (code "123") (name "Net-(X4H-KL)") (class "Default")
      (node (ref "R35") (pin "2") (pinfunction "2_2") (pintype "passive"))
      (node (ref "X4") (pin "8") (pinfunction "KL_8") (pintype "passive"))
    )
    (net (code "124") (name "Net-(X5A-KL)") (class "Default")
      (node (ref "R36") (pin "2") (pinfunction "2_2") (pintype "passive"))
      (node (ref "X5") (pin "1") (pinfunction "KL_1") (pintype "passive"))
    )
    (net (code "125") (name "Net-(X5B-KL)") (class "Default")
      (node (ref "R37") (pin "2") (pinfunction "2_2") (pintype "passive"))
      (node (ref "X5") (pin "2") (pinfunction "KL_2") (pintype "passive"))
    )
    (net (code "126") (name "Net-(X5C-KL)") (class "Default")
      (node (ref "R38") (pin "2") (pinfunction "2_2") (pintype "passive"))
      (node (ref "X5") (pin "3") (pinfunction "KL_3") (pintype "passive"))
    )
    (net (code "127") (name "Net-(X5D-KL)") (class "Default")
      (node (ref "R39") (pin "2") (pinfunction "2_2") (pintype "passive"))
      (node (ref "X5") (pin "4") (pinfunction "KL_4") (pintype "passive"))
    )
    (net (code "128") (name "Net-(X5E-KL)") (class "Default")
      (node (ref "R40") (pin "2") (pinfunction "2_2") (pintype "passive"))
      (node (ref "X5") (pin "5") (pinfunction "KL_5") (pintype "passive"))
    )
    (net (code "129") (name "Net-(X5F-KL)") (class "Default")
      (node (ref "R41") (pin "2") (pinfunction "2_2") (pintype "passive"))
      (node (ref "X5") (pin "6") (pinfunction "KL_6") (pintype "passive"))
    )
    (net (code "130") (name "Net-(X5G-KL)") (class "Default")
      (node (ref "R43") (pin "2") (pinfunction "2_2") (pintype "passive"))
      (node (ref "X5") (pin "7") (pinfunction "KL_7") (pintype "passive"))
    )
    (net (code "131") (name "Net-(X5H-KL)") (class "Default")
      (node (ref "R42") (pin "2") (pinfunction "2_2") (pintype "passive"))
      (node (ref "X5") (pin "8") (pinfunction "KL_8") (pintype "passive"))
    )
    (net (code "132") (name "Net-(X6A-KL)") (class "Default")
      (node (ref "R44") (pin "2") (pinfunction "2_2") (pintype "passive"))
      (node (ref "X6") (pin "1") (pinfunction "KL_1") (pintype "passive"))
    )
    (net (code "133") (name "Net-(X6B-KL)") (class "Default")
      (node (ref "R45") (pin "2") (pinfunction "2_2") (pintype "passive"))
      (node (ref "X6") (pin "2") (pinfunction "KL_2") (pintype "passive"))
    )
    (net (code "134") (name "Net-(X6C-KL)") (class "Default")
      (node (ref "R46") (pin "2") (pinfunction "2_2") (pintype "passive"))
      (node (ref "X6") (pin "3") (pinfunction "KL_3") (pintype "passive"))
    )
    (net (code "135") (name "Net-(X6D-KL)") (class "Default")
      (node (ref "R47") (pin "2") (pinfunction "2_2") (pintype "passive"))
      (node (ref "X6") (pin "4") (pinfunction "KL_4") (pintype "passive"))
    )
    (net (code "136") (name "Net-(X6E-KL)") (class "Default")
      (node (ref "R48") (pin "2") (pinfunction "2_2") (pintype "passive"))
      (node (ref "X6") (pin "5") (pinfunction "KL_5") (pintype "passive"))
    )
    (net (code "137") (name "Net-(X6F-KL)") (class "Default")
      (node (ref "R49") (pin "2") (pinfunction "2_2") (pintype "passive"))
      (node (ref "X6") (pin "6") (pinfunction "KL_6") (pintype "passive"))
    )
    (net (code "138") (name "Net-(X6G-KL)") (class "Default")
      (node (ref "R50") (pin "2") (pinfunction "2_2") (pintype "passive"))
      (node (ref "X6") (pin "7") (pinfunction "KL_7") (pintype "passive"))
    )
    (net (code "139") (name "Net-(X6H-KL)") (class "Default")
      (node (ref "R51") (pin "2") (pinfunction "2_2") (pintype "passive"))
      (node (ref "X6") (pin "8") (pinfunction "KL_8") (pintype "passive"))
    )
    (net (code "140") (name "Net-(X7A-KL)") (class "Default")
      (node (ref "R52") (pin "2") (pinfunction "2_2") (pintype "passive"))
      (node (ref "X7") (pin "1") (pinfunction "KL_1") (pintype "passive"))
    )
    (net (code "141") (name "Net-(X7B-KL)") (class "Default")
      (node (ref "R53") (pin "2") (pinfunction "2_2") (pintype "passive"))
      (node (ref "X7") (pin "2") (pinfunction "KL_2") (pintype "passive"))
    )
    (net (code "142") (name "Net-(X7C-KL)") (class "Default")
      (node (ref "R54") (pin "2") (pinfunction "2_2") (pintype "passive"))
      (node (ref "X7") (pin "3") (pinfunction "KL_3") (pintype "passive"))
    )
    (net (code "143") (name "Net-(X7D-KL)") (class "Default")
      (node (ref "R55") (pin "2") (pinfunction "2_2") (pintype "passive"))
      (node (ref "X7") (pin "4") (pinfunction "KL_4") (pintype "passive"))
    )
    (net (code "144") (name "Net-(X7E-KL)") (class "Default")
      (node (ref "R56") (pin "2") (pinfunction "2_2") (pintype "passive"))
      (node (ref "X7") (pin "5") (pinfunction "KL_5") (pintype "passive"))
    )
    (net (code "145") (name "Net-(X7F-KL)") (class "Default")
      (node (ref "R57") (pin "2") (pinfunction "2_2") (pintype "passive"))
      (node (ref "X7") (pin "6") (pinfunction "KL_6") (pintype "passive"))
    )
    (net (code "146") (name "Net-(X7G-KL)") (class "Default")
      (node (ref "R58") (pin "2") (pinfunction "2_2") (pintype "passive"))
      (node (ref "X7") (pin "7") (pinfunction "KL_7") (pintype "passive"))
    )
    (net (code "147") (name "Net-(X7H-KL)") (class "Default")
      (node (ref "R59") (pin "2") (pinfunction "2_2") (pintype "passive"))
      (node (ref "X7") (pin "8") (pinfunction "KL_8") (pintype "passive"))
    )
    (net (code "148") (name "Net-(X8A-KL)") (class "Default")
      (node (ref "R60") (pin "2") (pinfunction "2_2") (pintype "passive"))
      (node (ref "X8") (pin "1") (pinfunction "KL_1") (pintype "passive"))
    )
    (net (code "149") (name "Net-(X8B-KL)") (class "Default")
      (node (ref "R61") (pin "2") (pinfunction "2_2") (pintype "passive"))
      (node (ref "X8") (pin "2") (pinfunction "KL_2") (pintype "passive"))
    )
    (net (code "150") (name "Net-(X8C-KL)") (class "Default")
      (node (ref "R62") (pin "2") (pinfunction "2_2") (pintype "passive"))
      (node (ref "X8") (pin "3") (pinfunction "KL_3") (pintype "passive"))
    )
    (net (code "151") (name "Net-(X8D-KL)") (class "Default")
      (node (ref "R63") (pin "2") (pinfunction "2_2") (pintype "passive"))
      (node (ref "X8") (pin "4") (pinfunction "KL_4") (pintype "passive"))
    )
    (net (code "152") (name "Net-(X8E-KL)") (class "Default")
      (node (ref "R64") (pin "2") (pinfunction "2_2") (pintype "passive"))
      (node (ref "X8") (pin "5") (pinfunction "KL_5") (pintype "passive"))
    )
    (net (code "153") (name "Net-(X8F-KL)") (class "Default")
      (node (ref "R65") (pin "2") (pinfunction "2_2") (pintype "passive"))
      (node (ref "X8") (pin "6") (pinfunction "KL_6") (pintype "passive"))
    )
    (net (code "154") (name "Net-(X8G-KL)") (class "Default")
      (node (ref "R66") (pin "2") (pinfunction "2_2") (pintype "passive"))
      (node (ref "X8") (pin "7") (pinfunction "KL_7") (pintype "passive"))
    )
    (net (code "155") (name "Net-(X8H-KL)") (class "Default")
      (node (ref "R67") (pin "2") (pinfunction "2_2") (pintype "passive"))
      (node (ref "X8") (pin "8") (pinfunction "KL_8") (pintype "passive"))
    )
    (net (code "156") (name "Net-(X9A-KL)") (class "Default")
      (node (ref "R68") (pin "2") (pinfunction "2_2") (pintype "passive"))
      (node (ref "X9") (pin "1") (pinfunction "KL_1") (pintype "passive"))
    )
    (net (code "157") (name "Net-(X9B-KL)") (class "Default")
      (node (ref "R69") (pin "2") (pinfunction "2_2") (pintype "passive"))
      (node (ref "X9") (pin "2") (pinfunction "KL_2") (pintype "passive"))
    )
    (net (code "158") (name "Net-(X9C-KL)") (class "Default")
      (node (ref "R70") (pin "2") (pinfunction "2_2") (pintype "passive"))
      (node (ref "X9") (pin "3") (pinfunction "KL_3") (pintype "passive"))
    )
    (net (code "159") (name "Net-(X9D-KL)") (class "Default")
      (node (ref "R71") (pin "2") (pinfunction "2_2") (pintype "passive"))
      (node (ref "X9") (pin "4") (pinfunction "KL_4") (pintype "passive"))
    )
    (net (code "160") (name "Net-(X9E-KL)") (class "Default")
      (node (ref "R72") (pin "2") (pinfunction "2_2") (pintype "passive"))
      (node (ref "X9") (pin "5") (pinfunction "KL_5") (pintype "passive"))
    )
    (net (code "161") (name "Net-(X9F-KL)") (class "Default")
      (node (ref "R73") (pin "2") (pinfunction "2_2") (pintype "passive"))
      (node (ref "X9") (pin "6") (pinfunction "KL_6") (pintype "passive"))
    )
    (net (code "162") (name "Net-(X9G-KL)") (class "Default")
      (node (ref "R74") (pin "2") (pinfunction "2_2") (pintype "passive"))
      (node (ref "X9") (pin "7") (pinfunction "KL_7") (pintype "passive"))
    )
    (net (code "163") (name "Net-(X9H-KL)") (class "Default")
      (node (ref "R75") (pin "2") (pinfunction "2_2") (pintype "passive"))
      (node (ref "X9") (pin "8") (pinfunction "KL_8") (pintype "passive"))
    )
    (net (code "164") (name "VCC") (class "Default")
      (node (ref "C3") (pin "+") (pinfunction "+_+") (pintype "passive"))
      (node (ref "IC1") (pin "20") (pinfunction "AVCC_20") (pintype "power_in"))
      (node (ref "IC1") (pin "21") (pinfunction "AREF_21") (pintype "passive"))
      (node (ref "IC1") (pin "7") (pinfunction "VCC_7") (pintype "power_in"))
      (node (ref "R1") (pin "1") (pinfunction "1_1") (pintype "passive"))
      (node (ref "S-B1") (pin "7") (pinfunction "SCLR_7") (pintype "input"))
      (node (ref "S-B2") (pin "7") (pinfunction "SCLR_7") (pintype "input"))
      (node (ref "S-B3") (pin "7") (pinfunction "SCLR_7") (pintype "input"))
      (node (ref "S-G1") (pin "7") (pinfunction "SCLR_7") (pintype "input"))
      (node (ref "S-G2") (pin "7") (pinfunction "SCLR_7") (pintype "input"))
      (node (ref "S-G3") (pin "7") (pinfunction "SCLR_7") (pintype "input"))
      (node (ref "S-R1") (pin "7") (pinfunction "SCLR_7") (pintype "input"))
      (node (ref "S-R2") (pin "7") (pinfunction "SCLR_7") (pintype "input"))
      (node (ref "S-R3") (pin "7") (pinfunction "SCLR_7") (pintype "input"))
    )
    (net (code "165") (name "unconnected-(IC1-PB1(OC1A)-Pad15)") (class "Default")
      (node (ref "IC1") (pin "15") (pinfunction "PB1(OC1A)_15") (pintype "bidirectional"))
    )
    (net (code "166") (name "unconnected-(IC1-PB2(SS{slash}OC1B)-Pad16)") (class "Default")
      (node (ref "IC1") (pin "16") (pinfunction "PB2(SS/OC1B)_16") (pintype "bidirectional"))
    )
    (net (code "167") (name "unconnected-(IC1-PB4(MISO)-Pad18)") (class "Default")
      (node (ref "IC1") (pin "18") (pinfunction "PB4(MISO)_18") (pintype "bidirectional"))
    )
    (net (code "168") (name "unconnected-(IC1-PB5(SCK)-Pad19)") (class "Default")
      (node (ref "IC1") (pin "19") (pinfunction "PB5(SCK)_19") (pintype "bidirectional"))
    )
    (net (code "169") (name "unconnected-(IC1-PC0(ADC0)-Pad23)") (class "Default")
      (node (ref "IC1") (pin "23") (pinfunction "PC0(ADC0)_23") (pintype "bidirectional"))
    )
    (net (code "170") (name "unconnected-(IC1-PC1(ADC1)-Pad24)") (class "Default")
      (node (ref "IC1") (pin "24") (pinfunction "PC1(ADC1)_24") (pintype "bidirectional"))
    )
    (net (code "171") (name "unconnected-(IC1-PC2(ADC2)-Pad25)") (class "Default")
      (node (ref "IC1") (pin "25") (pinfunction "PC2(ADC2)_25") (pintype "bidirectional"))
    )
    (net (code "172") (name "unconnected-(IC1-PC3(ADC3)-Pad26)") (class "Default")
      (node (ref "IC1") (pin "26") (pinfunction "PC3(ADC3)_26") (pintype "bidirectional"))
    )
    (net (code "173") (name "unconnected-(IC1-PC4(ADC4{slash}SDA)-Pad27)") (class "Default")
      (node (ref "IC1") (pin "27") (pinfunction "PC4(ADC4/SDA)_27") (pintype "bidirectional"))
    )
    (net (code "174") (name "unconnected-(IC1-PC5(ADC5{slash}SCL)-Pad28)") (class "Default")
      (node (ref "IC1") (pin "28") (pinfunction "PC5(ADC5/SCL)_28") (pintype "bidirectional"))
    )
    (net (code "175") (name "unconnected-(IC1-PD5(T1)-Pad11)") (class "Default")
      (node (ref "IC1") (pin "11") (pinfunction "PD5(T1)_11") (pintype "bidirectional"))
    )
    (net (code "176") (name "unconnected-(IC1-PD6(AIN0)-Pad12)") (class "Default")
      (node (ref "IC1") (pin "12") (pinfunction "PD6(AIN0)_12") (pintype "bidirectional"))
    )
    (net (code "177") (name "unconnected-(IC1-PD7(AIN1)-Pad13)") (class "Default")
      (node (ref "IC1") (pin "13") (pinfunction "PD7(AIN1)_13") (pintype "bidirectional"))
    )
    (net (code "178") (name "unconnected-(S-B3A-DO-Pad9)") (class "Default")
      (node (ref "S-B3") (pin "9") (pinfunction "DO_9") (pintype "output"))
    )
    (net (code "179") (name "unconnected-(S-G3A-DO-Pad9)") (class "Default")
      (node (ref "S-G3") (pin "9") (pinfunction "DO_9") (pintype "output"))
    )
    (net (code "180") (name "unconnected-(S-R3A-DO-Pad9)") (class "Default")
      (node (ref "S-R3") (pin "9") (pinfunction "DO_9") (pintype "output"))
    )
  )
)
